# SeniorDesignV2.net
KiCad netlist of a schematic drawn in EasyEDA
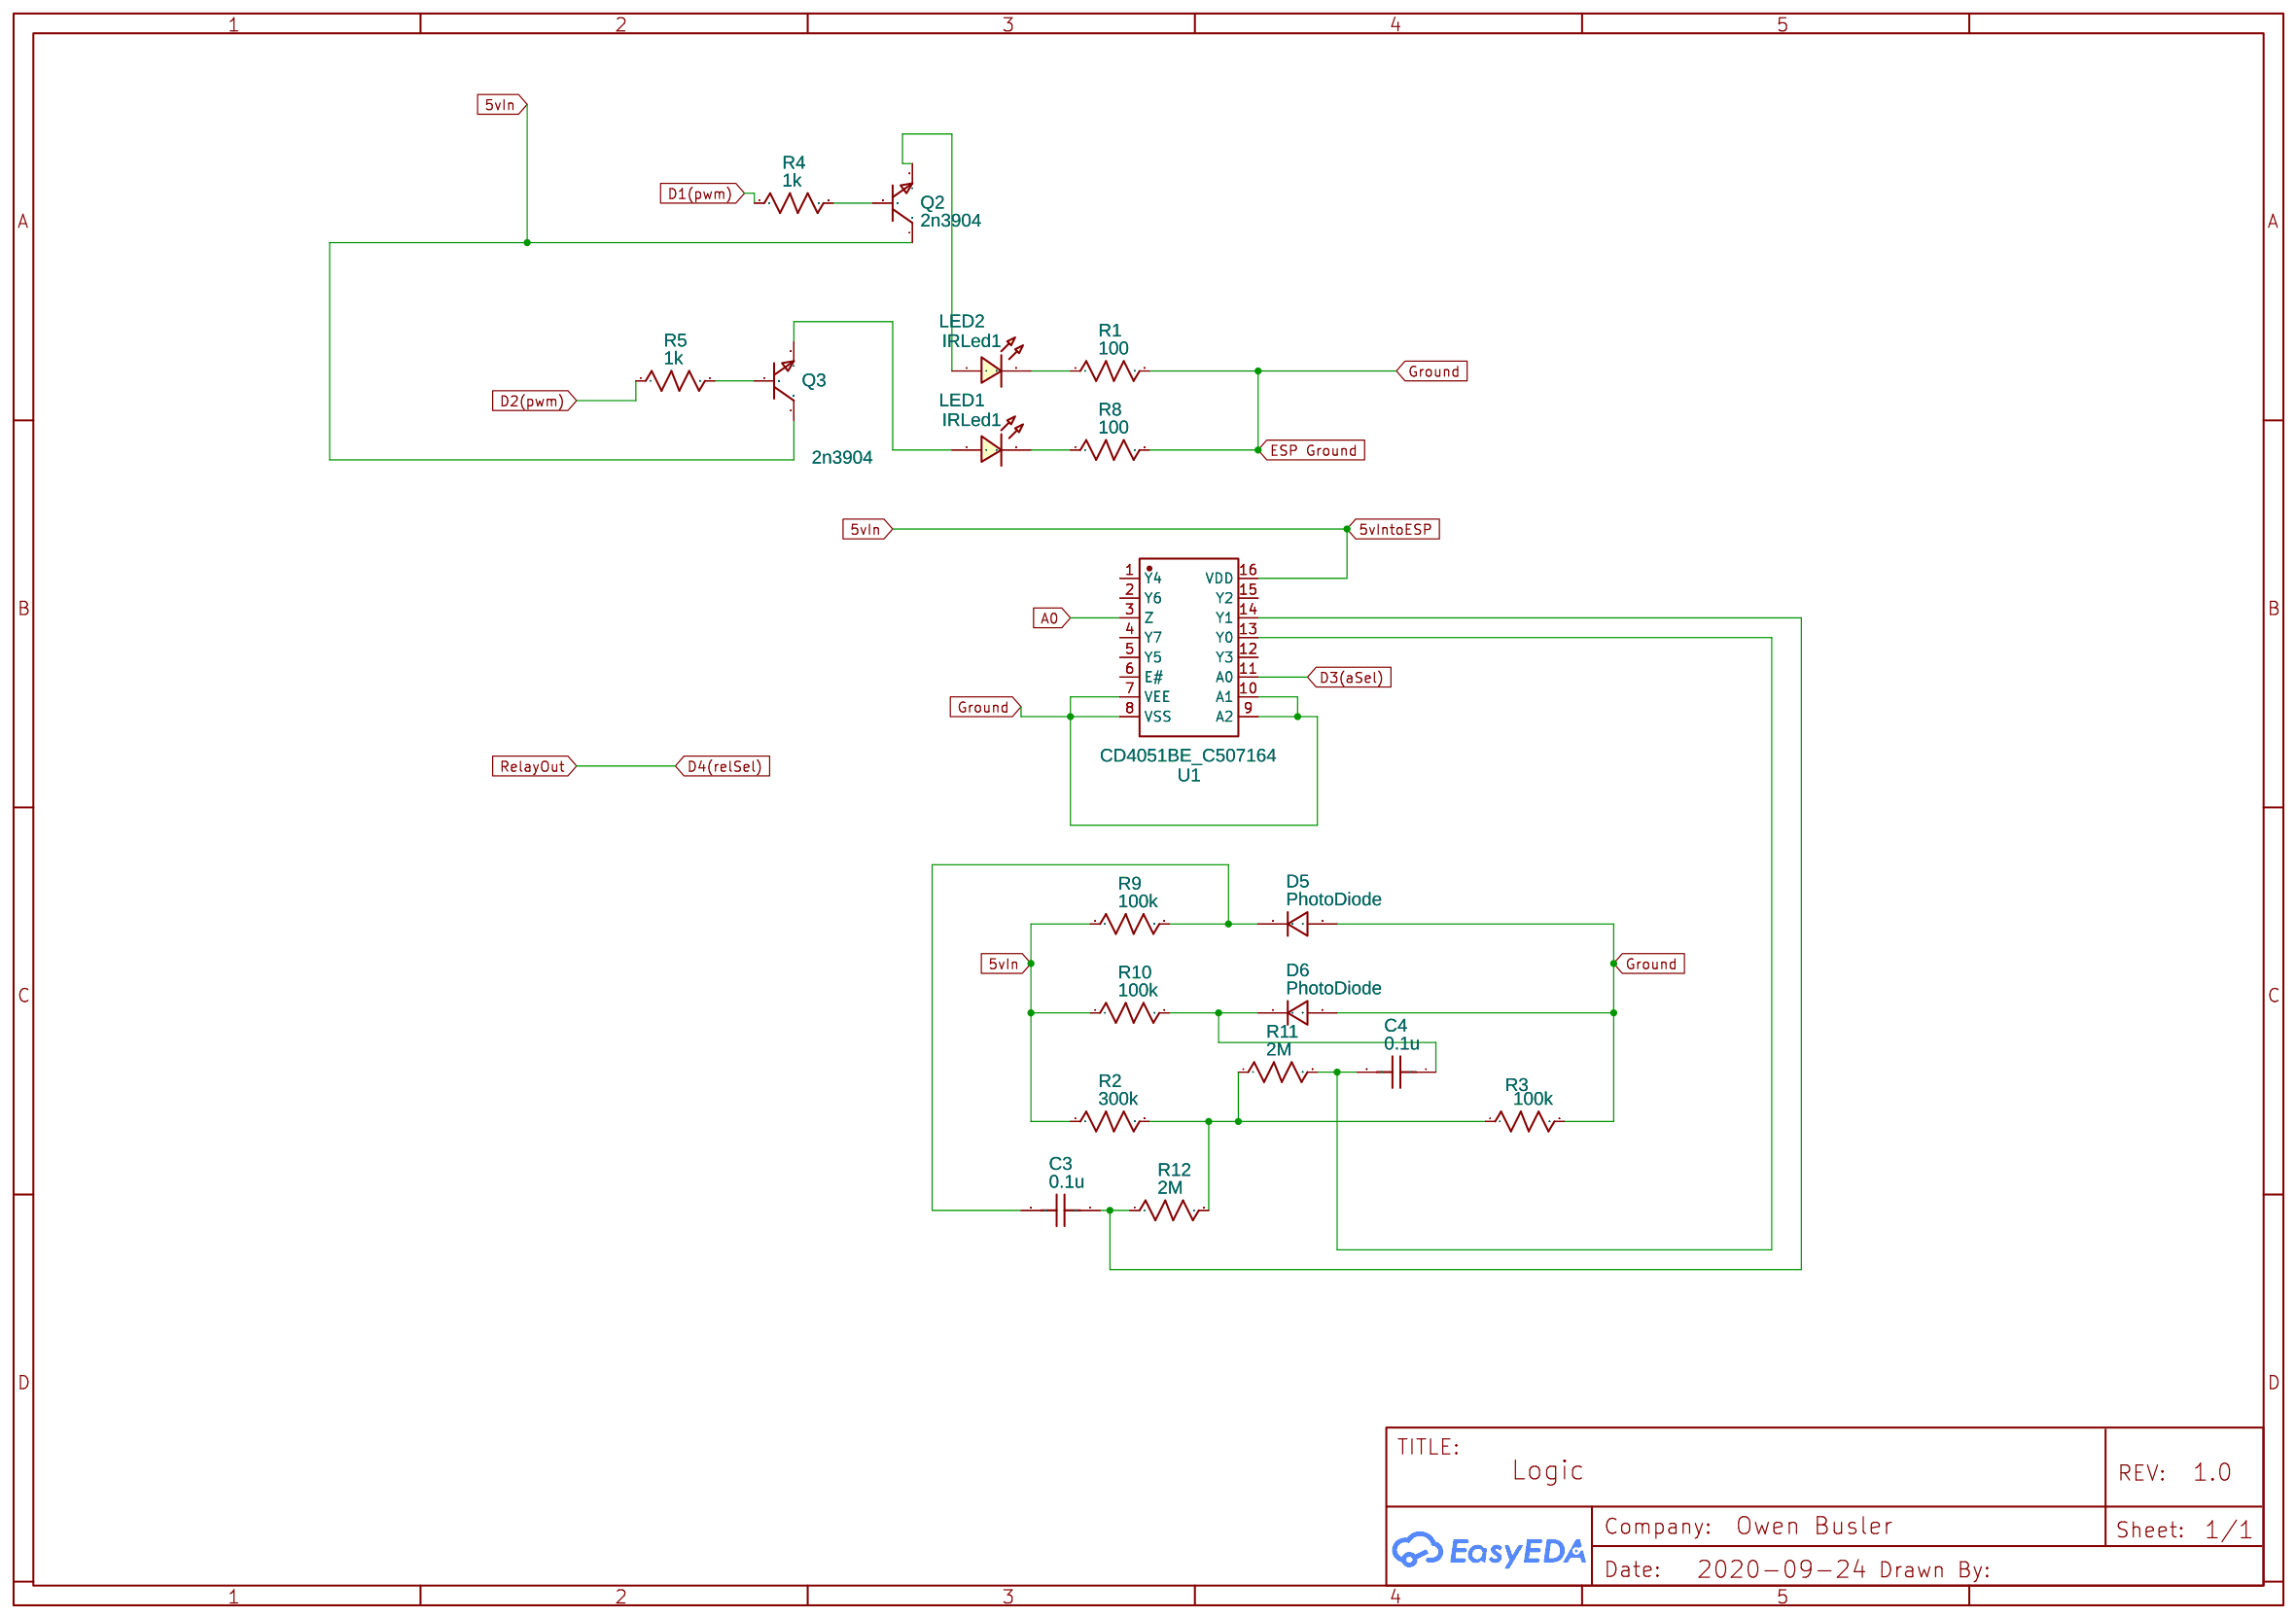
[diagram p0: LogicSch]
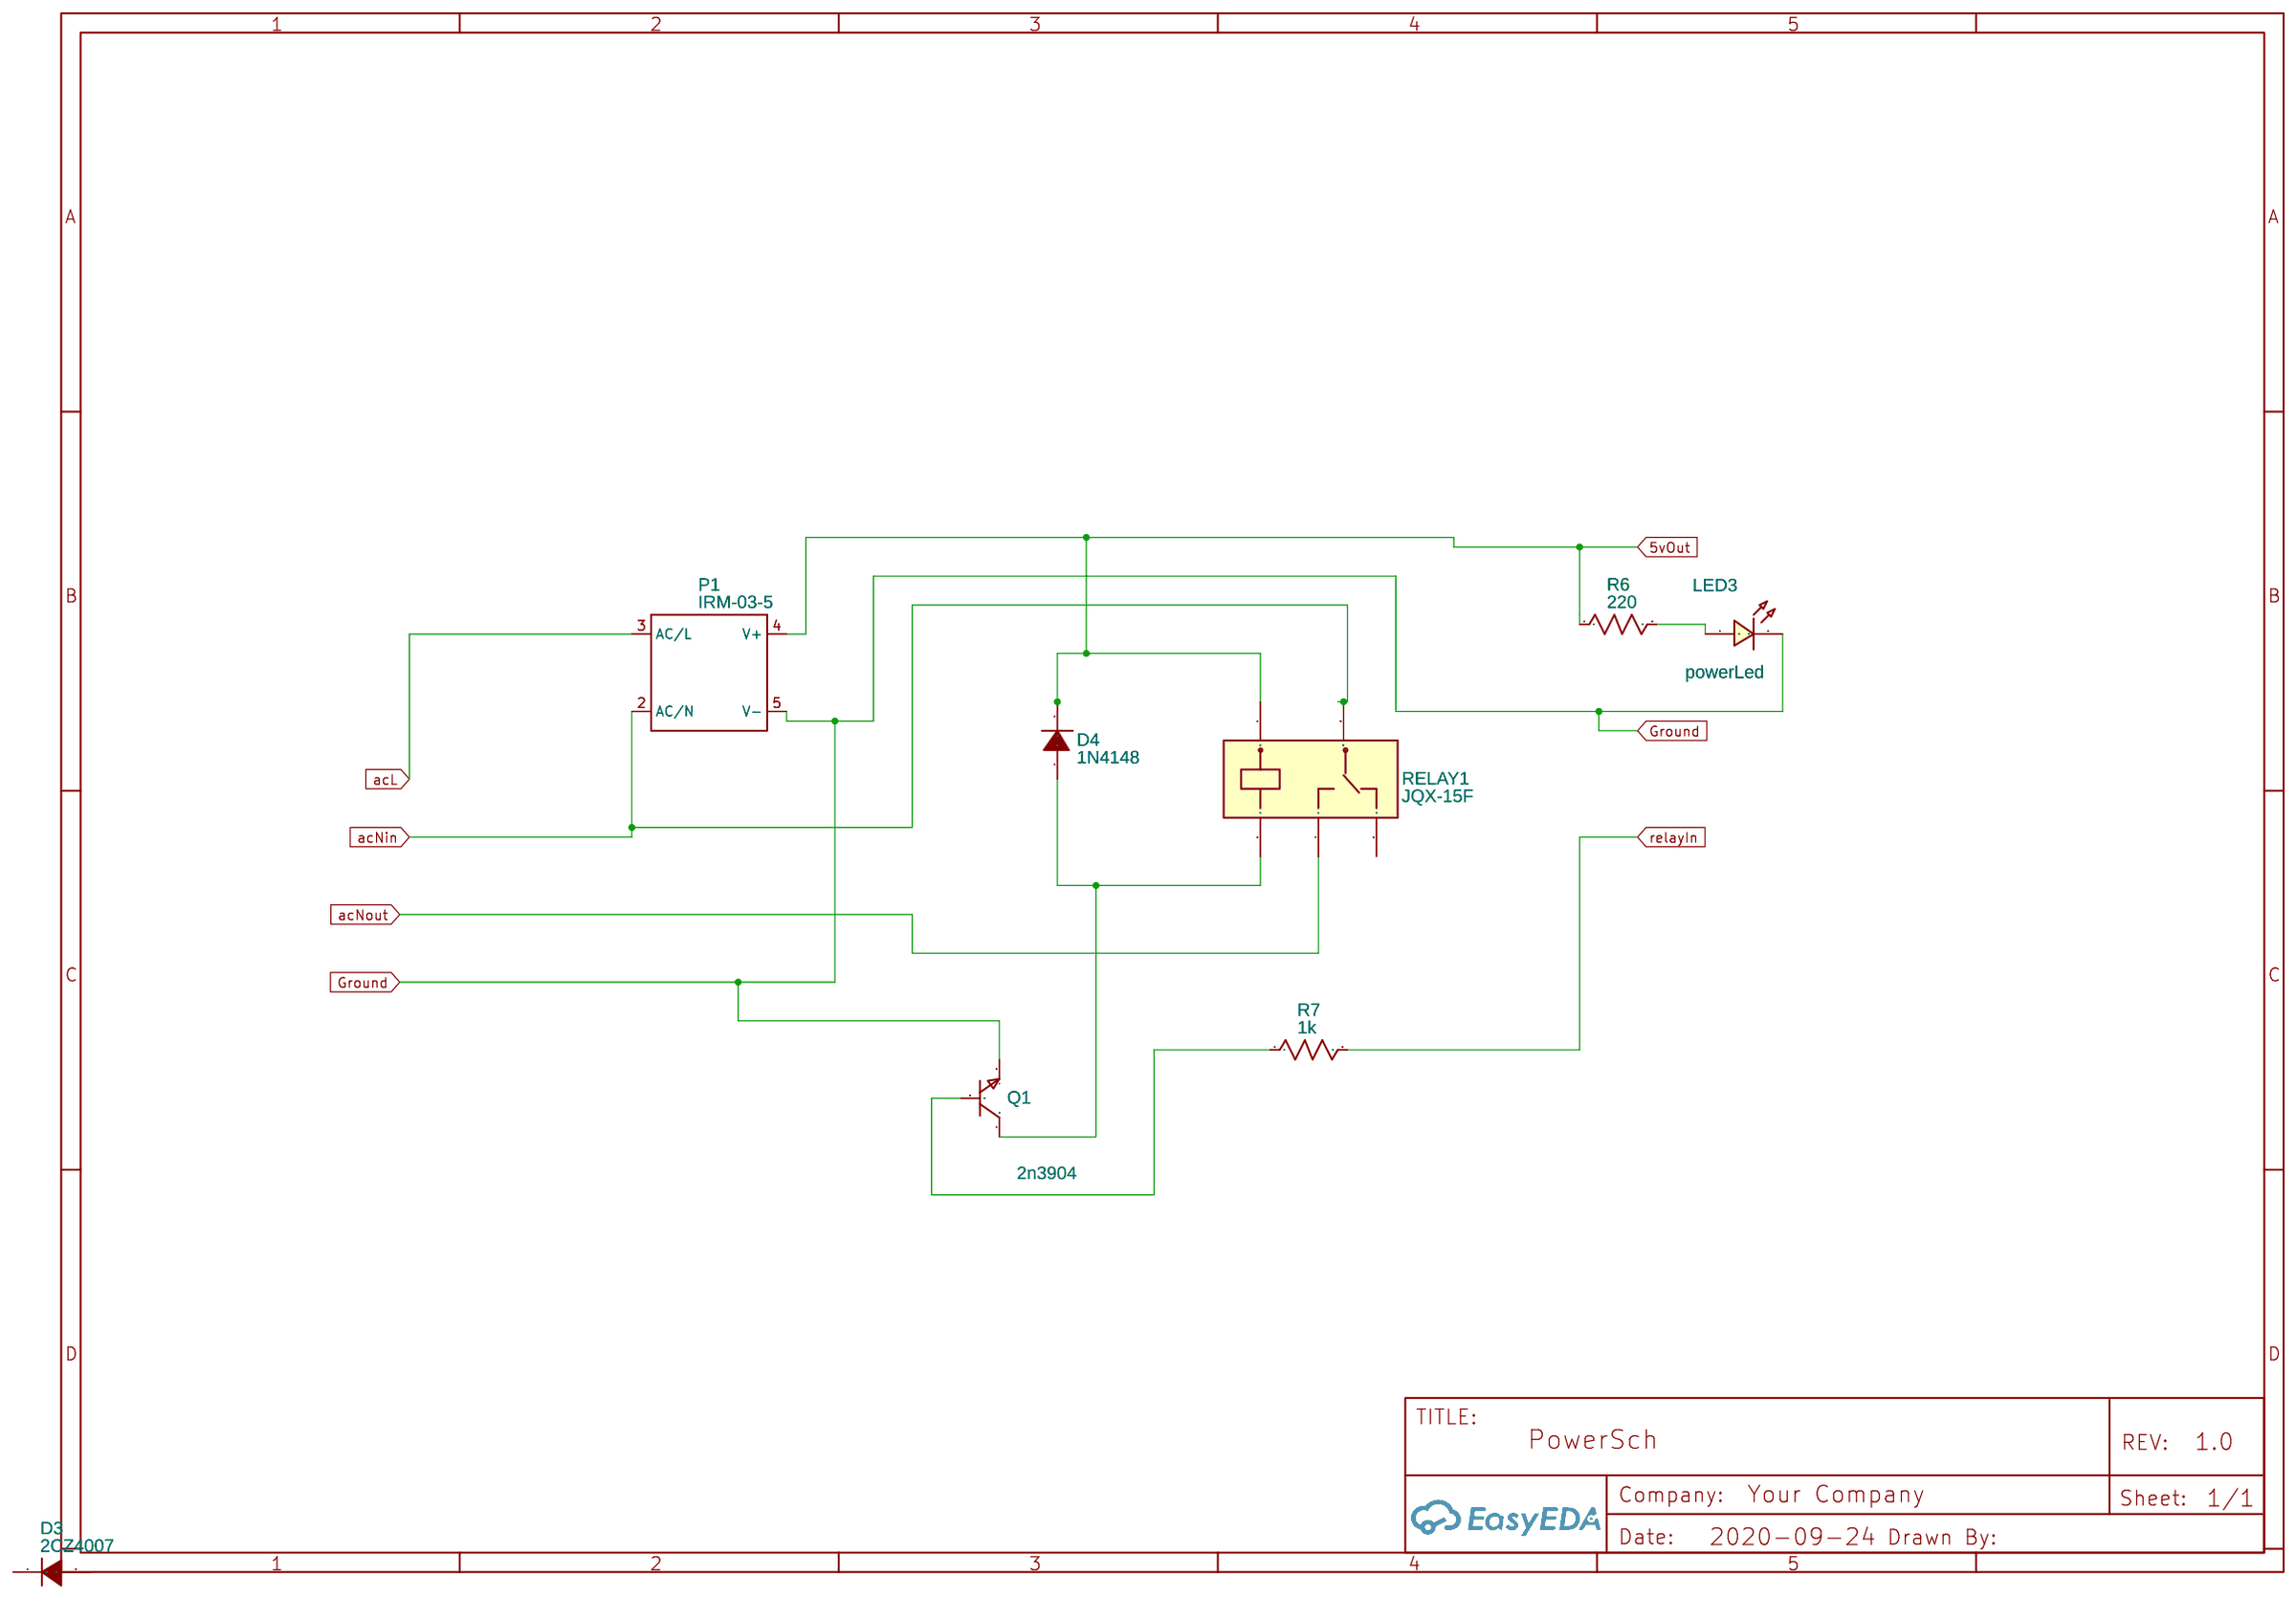
[diagram p1: PowerSch]

(export (version "E")
  (design (tool "Eeschema 10.0.6"))
  (components
    (comp (ref "C3") (value "0.1u") (libsource (lib "") (part "C_0603_US")))
    (comp (ref "C4") (value "0.1u") (libsource (lib "") (part "C_0603_US")))
    (comp (ref "D5")
      (value "PhotoDiode")
      (fields (field (name "BOM_Manufacturer Part") "1N4007W") (field (name "BOM_Supplier Part") "C328592"))
      (libsource (lib "") (part "1N4007W"))
    )
    (comp (ref "D6")
      (value "PhotoDiode")
      (fields (field (name "BOM_Manufacturer Part") "1N4007W") (field (name "BOM_Supplier Part") "C328592"))
      (libsource (lib "") (part "1N4007W"))
    )
    (comp (ref "LED1")
      (value "IRLed1")
      (fields
        (field (name "BOM_Manufacturer Part") "19-217/R6C-AL1M2VY/3T")
        (field (name "BOM_Supplier Part") "C72044")
      )
      (libsource (lib "") (part "LED-0603_R"))
    )
    (comp (ref "LED2")
      (value "IRLed1")
      (fields
        (field (name "BOM_Manufacturer Part") "19-217/R6C-AL1M2VY/3T")
        (field (name "BOM_Supplier Part") "C72044")
      )
      (libsource (lib "") (part "LED-0603_R"))
    )
    (comp (ref "Q2") (value "2n3904") (libsource (lib "") (part "2n3904")))
    (comp (ref "Q3") (value "2n3904") (libsource (lib "") (part "2n3904")))
    (comp (ref "R1") (value "100") (libsource (lib "") (part "R_0603_US")))
    (comp (ref "R2") (value "300k") (libsource (lib "") (part "R_0603_US")))
    (comp (ref "R3") (value "100k") (libsource (lib "") (part "R_0603_US")))
    (comp (ref "R4") (value "1k") (libsource (lib "") (part "R_0603_US")))
    (comp (ref "R5") (value "1k") (libsource (lib "") (part "R_0603_US")))
    (comp (ref "R8") (value "100") (libsource (lib "") (part "R_0603_US")))
    (comp (ref "R9") (value "100k") (libsource (lib "") (part "R_0603_US")))
    (comp (ref "R10") (value "100k") (libsource (lib "") (part "R_0603_US")))
    (comp (ref "R11") (value "2M") (libsource (lib "") (part "R_0603_US")))
    (comp (ref "R12") (value "2M") (libsource (lib "") (part "R_0603_US")))
    (comp (ref "U1")
      (value "CD4051BE_C507164")
      (fields (field (name "BOM_Manufacturer Part") "CD4051BE") (field (name "BOM_Supplier Part") "C507164"))
      (libsource (lib "") (part "CD4051BE_C507164"))
    )
    (comp (ref "D3")
      (value "2CZ4007")
      (fields (field (name "BOM_Supplier Part") "C85712"))
      (libsource (lib "") (part "2CZ4007"))
    )
    (comp (ref "D4")
      (value "1N4148")
      (fields (field (name "BOM_Supplier Part") "C14516"))
      (libsource (lib "") (part "1N4148"))
    )
    (comp (ref "LED3")
      (value "powerLed")
      (fields
        (field (name "BOM_Manufacturer Part") "19-217/R6C-AL1M2VY/3T")
        (field (name "BOM_Supplier Part") "C72044")
      )
      (libsource (lib "") (part "LED-0603_R"))
    )
    (comp (ref "P1") (value "IRM-03-5") (libsource (lib "") (part "IRM-03-5")))
    (comp (ref "Q1") (value "2n3904") (libsource (lib "") (part "2n3904")))
    (comp (ref "R6") (value "220") (libsource (lib "") (part "R_0603_US")))
    (comp (ref "R7") (value "1k") (libsource (lib "") (part "R_0603_US")))
    (comp (ref "RELAY1")
      (value "JQX-15F")
      (fields
        (field (name "BOM_Manufacturer Part") "JQX-105F-1/012D-1HS")
        (field (name "BOM_Supplier Part") "C3631")
      )
      (libsource (lib "") (part "JQX-15F"))
    )
  )
  (nets
    (net (code "1") (name "5vIn") (class "Default")
      (node (ref "Q2") (pin "1") (pinfunction "C_1") (pintype "unspecified"))
      (node (ref "Q3") (pin "1") (pinfunction "C_1") (pintype "unspecified"))
      (node (ref "R10") (pin "1") (pinfunction "1_1") (pintype "unspecified"))
      (node (ref "R2") (pin "1") (pinfunction "1_1") (pintype "unspecified"))
      (node (ref "R9") (pin "1") (pinfunction "1_1") (pintype "unspecified"))
      (node (ref "U1") (pin "16") (pinfunction "VDD_16") (pintype "unspecified"))
    )
    (net (code "2") (name "5vOut") (class "Default")
      (node (ref "D4") (pin "2") (pinfunction "C_2") (pintype "unspecified"))
      (node (ref "P1") (pin "4") (pinfunction "V+_4") (pintype "bidirectional"))
      (node (ref "R6") (pin "1") (pinfunction "1_1") (pintype "unspecified"))
      (node (ref "RELAY1") (pin "1") (pinfunction "1_1") (pintype "input"))
    )
    (net (code "3") (name "A0") (class "Default")
      (node (ref "U1") (pin "3") (pinfunction "Z_3") (pintype "unspecified"))
    )
    (net (code "4") (name "D1(pwm)") (class "Default")
      (node (ref "R4") (pin "1") (pinfunction "1_1") (pintype "unspecified"))
    )
    (net (code "5") (name "D2(pwm)") (class "Default")
      (node (ref "R5") (pin "1") (pinfunction "1_1") (pintype "unspecified"))
    )
    (net (code "6") (name "D3(aSel)") (class "Default")
      (node (ref "U1") (pin "11") (pinfunction "A0_11") (pintype "unspecified"))
    )
    (net (code "8") (name "ESP Ground") (class "Default")
      (node (ref "D5") (pin "2") (pinfunction "2_2") (pintype "unspecified"))
      (node (ref "D6") (pin "2") (pinfunction "2_2") (pintype "unspecified"))
      (node (ref "LED3") (pin "2") (pinfunction "2_2") (pintype "unspecified"))
      (node (ref "P1") (pin "5") (pinfunction "V-_5") (pintype "bidirectional"))
      (node (ref "Q1") (pin "3") (pinfunction "E_3") (pintype "unspecified"))
      (node (ref "R1") (pin "2") (pinfunction "2_2") (pintype "unspecified"))
      (node (ref "R3") (pin "2") (pinfunction "2_2") (pintype "unspecified"))
      (node (ref "R8") (pin "2") (pinfunction "2_2") (pintype "unspecified"))
      (node (ref "U1") (pin "10") (pinfunction "A1_10") (pintype "unspecified"))
      (node (ref "U1") (pin "7") (pinfunction "VEE_7") (pintype "unspecified"))
      (node (ref "U1") (pin "8") (pinfunction "VSS_8") (pintype "unspecified"))
      (node (ref "U1") (pin "9") (pinfunction "A2_9") (pintype "unspecified"))
    )
    (net (code "9") (name "Net-(C3-Pad2)") (class "Default")
      (node (ref "C3") (pin "2") (pinfunction "2_2") (pintype "unspecified"))
      (node (ref "D5") (pin "1") (pinfunction "1_1") (pintype "unspecified"))
      (node (ref "R9") (pin "2") (pinfunction "2_2") (pintype "unspecified"))
    )
    (net (code "10") (name "Net-(C4-Pad1)") (class "Default")
      (node (ref "C4") (pin "1") (pinfunction "1_1") (pintype "unspecified"))
      (node (ref "D6") (pin "1") (pinfunction "1_1") (pintype "unspecified"))
      (node (ref "R10") (pin "2") (pinfunction "2_2") (pintype "unspecified"))
    )
    (net (code "11") (name "Net-(D4-A)") (class "Default")
      (node (ref "D4") (pin "1") (pinfunction "A_1") (pintype "unspecified"))
      (node (ref "Q1") (pin "1") (pinfunction "C_1") (pintype "unspecified"))
      (node (ref "RELAY1") (pin "2") (pinfunction "2_2") (pintype "input"))
    )
    (net (code "12") (name "Net-(LED1-Pad2)") (class "Default")
      (node (ref "LED1") (pin "2") (pinfunction "2_2") (pintype "unspecified"))
      (node (ref "R8") (pin "1") (pinfunction "1_1") (pintype "unspecified"))
    )
    (net (code "13") (name "Net-(LED2-Pad2)") (class "Default")
      (node (ref "LED2") (pin "2") (pinfunction "2_2") (pintype "unspecified"))
      (node (ref "R1") (pin "1") (pinfunction "1_1") (pintype "unspecified"))
    )
    (net (code "14") (name "Net-(LED3-Pad1)") (class "Default")
      (node (ref "LED3") (pin "1") (pinfunction "1_1") (pintype "unspecified"))
      (node (ref "R6") (pin "2") (pinfunction "2_2") (pintype "unspecified"))
    )
    (net (code "15") (name "Net-(Q1-B)") (class "Default")
      (node (ref "Q1") (pin "2") (pinfunction "B_2") (pintype "unspecified"))
      (node (ref "R7") (pin "1") (pinfunction "1_1") (pintype "unspecified"))
    )
    (net (code "16") (name "Net-(Q2-B)") (class "Default")
      (node (ref "Q2") (pin "2") (pinfunction "B_2") (pintype "unspecified"))
      (node (ref "R4") (pin "2") (pinfunction "2_2") (pintype "unspecified"))
    )
    (net (code "17") (name "Net-(Q2-E)") (class "Default")
      (node (ref "LED2") (pin "1") (pinfunction "1_1") (pintype "unspecified"))
      (node (ref "Q2") (pin "3") (pinfunction "E_3") (pintype "unspecified"))
    )
    (net (code "18") (name "Net-(Q3-B)") (class "Default")
      (node (ref "Q3") (pin "2") (pinfunction "B_2") (pintype "unspecified"))
      (node (ref "R5") (pin "2") (pinfunction "2_2") (pintype "unspecified"))
    )
    (net (code "19") (name "Net-(Q3-E)") (class "Default")
      (node (ref "LED1") (pin "1") (pinfunction "1_1") (pintype "unspecified"))
      (node (ref "Q3") (pin "3") (pinfunction "E_3") (pintype "unspecified"))
    )
    (net (code "20") (name "Net-(R11-Pad1)") (class "Default")
      (node (ref "R11") (pin "1") (pinfunction "1_1") (pintype "unspecified"))
      (node (ref "R12") (pin "2") (pinfunction "2_2") (pintype "unspecified"))
      (node (ref "R2") (pin "2") (pinfunction "2_2") (pintype "unspecified"))
      (node (ref "R3") (pin "1") (pinfunction "1_1") (pintype "unspecified"))
    )
    (net (code "21") (name "Net-(U1-Y0)") (class "Default")
      (node (ref "C4") (pin "2") (pinfunction "2_2") (pintype "unspecified"))
      (node (ref "R11") (pin "2") (pinfunction "2_2") (pintype "unspecified"))
      (node (ref "U1") (pin "13") (pinfunction "Y0_13") (pintype "unspecified"))
    )
    (net (code "22") (name "Net-(U1-Y1)") (class "Default")
      (node (ref "C3") (pin "1") (pinfunction "1_1") (pintype "unspecified"))
      (node (ref "R12") (pin "1") (pinfunction "1_1") (pintype "unspecified"))
      (node (ref "U1") (pin "14") (pinfunction "Y1_14") (pintype "unspecified"))
    )
    (net (code "23") (name "acL") (class "Default")
      (node (ref "P1") (pin "3") (pinfunction "AC/L_3") (pintype "bidirectional"))
    )
    (net (code "24") (name "acNin") (class "Default")
      (node (ref "P1") (pin "2") (pinfunction "AC/N_2") (pintype "bidirectional"))
      (node (ref "RELAY1") (pin "5") (pinfunction "5_5") (pintype "unspecified"))
    )
    (net (code "25") (name "acNout") (class "Default")
      (node (ref "RELAY1") (pin "4") (pinfunction "4_4") (pintype "input"))
    )
    (net (code "26") (name "relayIn") (class "Default")
      (node (ref "R7") (pin "2") (pinfunction "2_2") (pintype "unspecified"))
    )
    (net (code "27") (name "unconnected-(D3-A-Pad2)") (class "Default")
      (node (ref "D3") (pin "2") (pinfunction "A_2") (pintype "unspecified"))
    )
    (net (code "28") (name "unconnected-(D3-C-Pad1)") (class "Default")
      (node (ref "D3") (pin "1") (pinfunction "C_1") (pintype "unspecified"))
    )
    (net (code "29") (name "unconnected-(RELAY1-Pad3)") (class "Default")
      (node (ref "RELAY1") (pin "3") (pinfunction "3_3") (pintype "input"))
    )
    (net (code "30") (name "unconnected-(U1-E#-Pad6)") (class "Default")
      (node (ref "U1") (pin "6") (pinfunction "E#_6") (pintype "unspecified"))
    )
    (net (code "31") (name "unconnected-(U1-Y2-Pad15)") (class "Default")
      (node (ref "U1") (pin "15") (pinfunction "Y2_15") (pintype "unspecified"))
    )
    (net (code "32") (name "unconnected-(U1-Y3-Pad12)") (class "Default")
      (node (ref "U1") (pin "12") (pinfunction "Y3_12") (pintype "unspecified"))
    )
    (net (code "33") (name "unconnected-(U1-Y4-Pad1)") (class "Default")
      (node (ref "U1") (pin "1") (pinfunction "Y4_1") (pintype "unspecified"))
    )
    (net (code "34") (name "unconnected-(U1-Y5-Pad5)") (class "Default")
      (node (ref "U1") (pin "5") (pinfunction "Y5_5") (pintype "unspecified"))
    )
    (net (code "35") (name "unconnected-(U1-Y6-Pad2)") (class "Default")
      (node (ref "U1") (pin "2") (pinfunction "Y6_2") (pintype "unspecified"))
    )
    (net (code "36") (name "unconnected-(U1-Y7-Pad4)") (class "Default")
      (node (ref "U1") (pin "4") (pinfunction "Y7_4") (pintype "unspecified"))
    )
  )
)
